# Polarization_Contol.net
KiCad netlist of a schematic drawn in EasyEDA
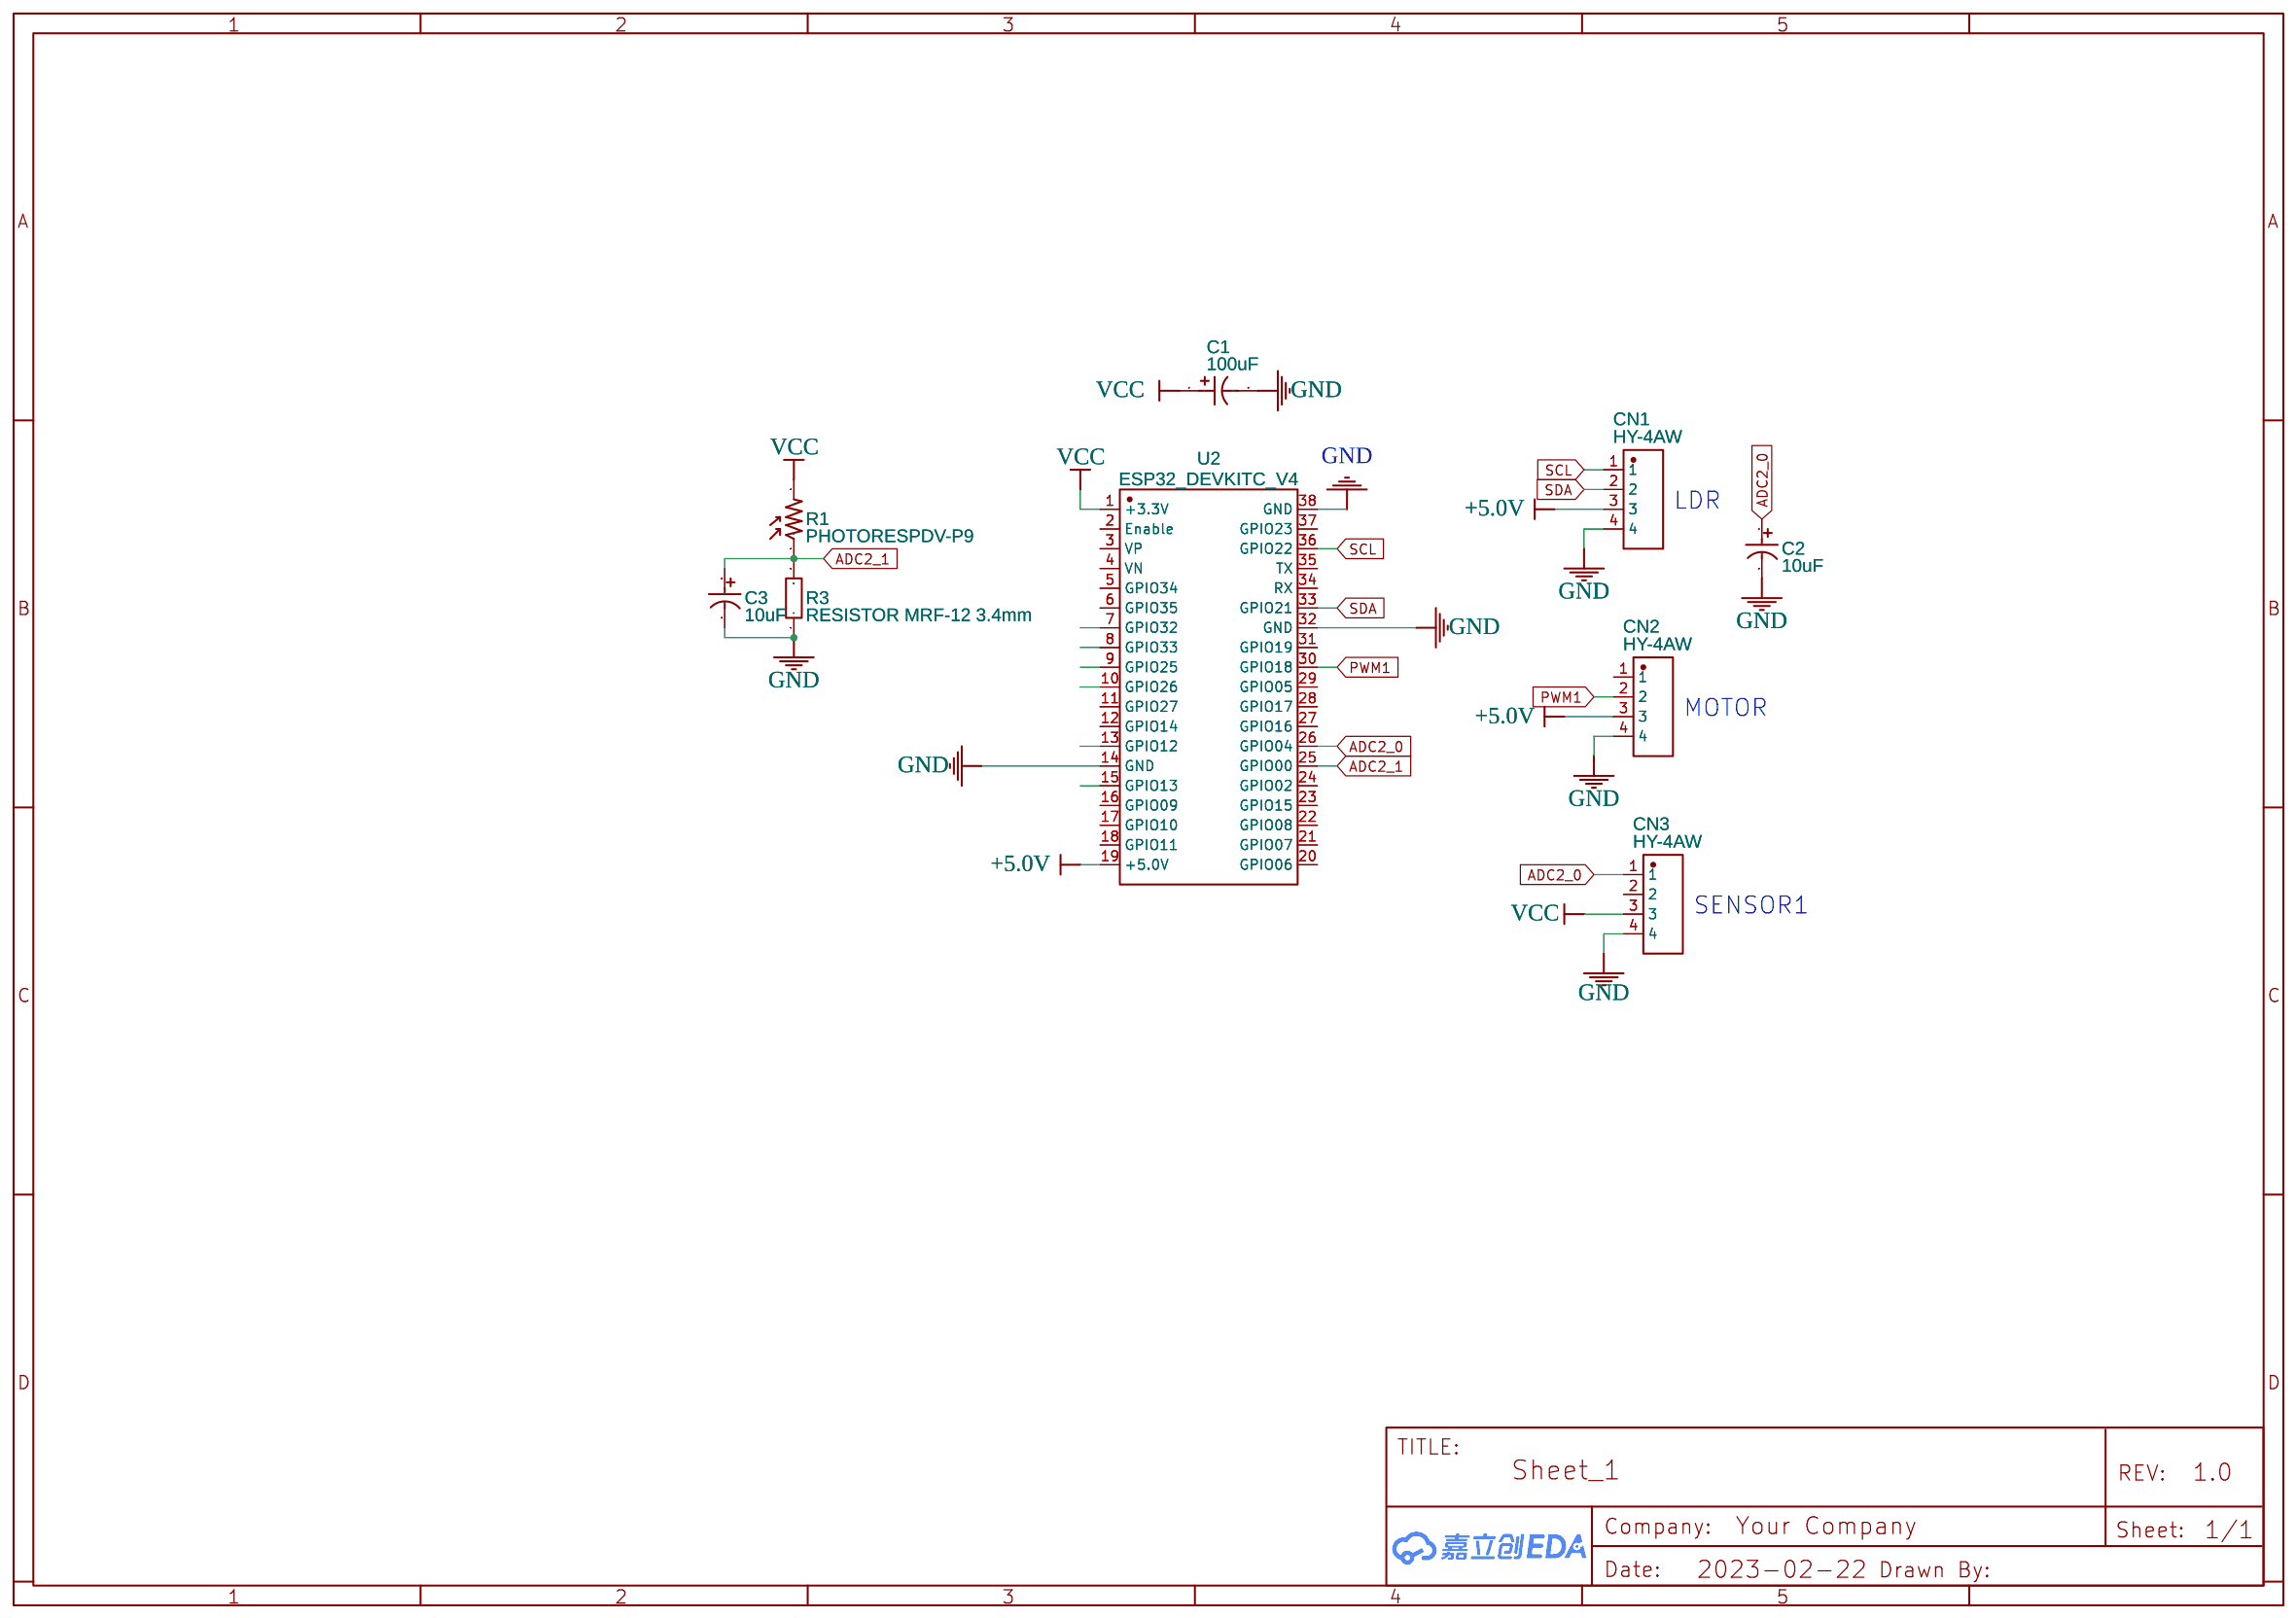
[diagram p0: Sheet_1]
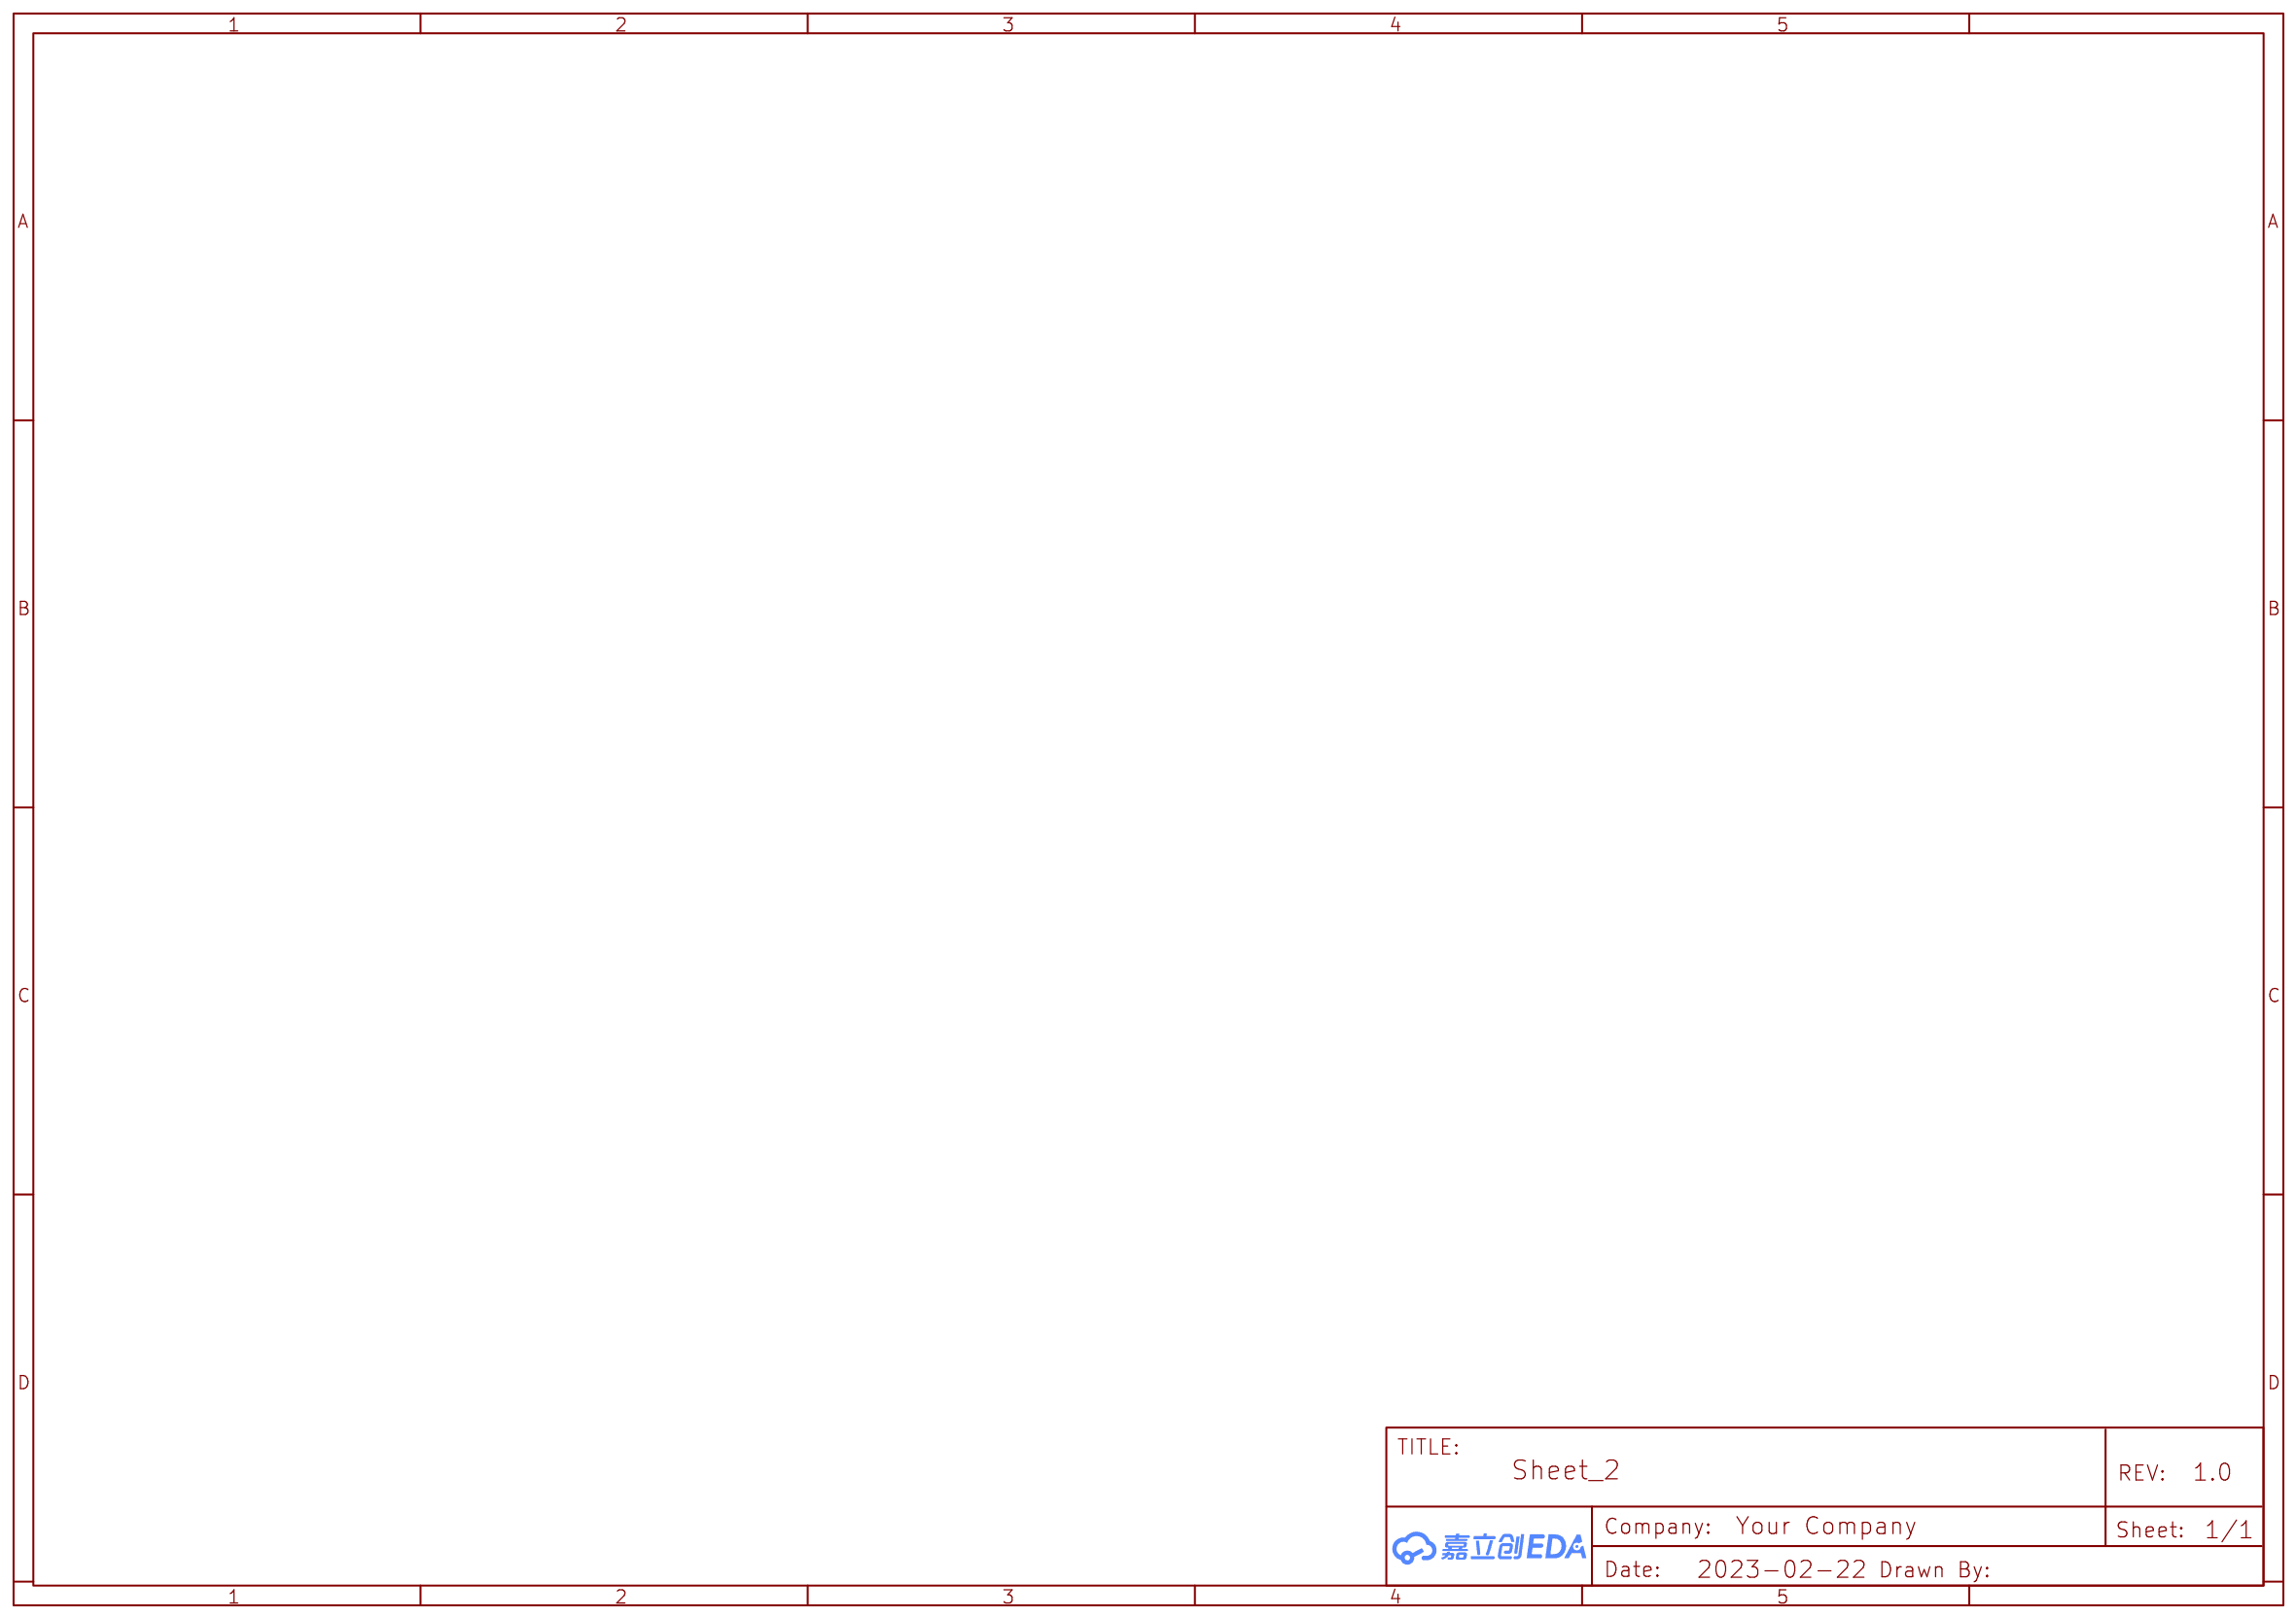
[diagram p1: Sheet_2]

(export (version "E")
  (design (tool "Eeschema 10.0.6"))
  (components
    (comp (ref "C1")
      (value "100uF")
      (fields
        (field (name "BOM_Manufacturer Part") "25V100uF CD110")
        (field (name "BOM_Supplier Part") "C2960218")
      )
      (libsource (lib "") (part "25V100UF CD110"))
    )
    (comp (ref "C2")
      (value "10uF")
      (fields
        (field (name "BOM_Manufacturer Part") "KM476M016D11RR0VH2FP0")
        (field (name "BOM_Supplier Part") "C22320")
      )
      (libsource (lib "") (part "47uF 16V Aluminum electrolytic capacitors"))
    )
    (comp (ref "C3")
      (value "10uF")
      (fields
        (field (name "BOM_Manufacturer Part") "KM476M016D11RR0VH2FP0")
        (field (name "BOM_Supplier Part") "C22320")
      )
      (libsource (lib "") (part "47uF 16V Aluminum electrolytic capacitors"))
    )
    (comp (ref "CN1")
      (value "HY-4AW")
      (fields (field (name "BOM_Supplier Part") "C146068"))
      (libsource (lib "") (part "HY-4AW"))
    )
    (comp (ref "CN2")
      (value "HY-4AW")
      (fields (field (name "BOM_Supplier Part") "C146068"))
      (libsource (lib "") (part "HY-4AW"))
    )
    (comp (ref "CN3")
      (value "HY-4AW")
      (fields (field (name "BOM_Supplier Part") "C146068"))
      (libsource (lib "") (part "HY-4AW"))
    )
    (comp (ref "R1") (value "PHOTORESPDV-P9") (libsource (lib "") (part "PHOTORESPDV-P9")))
    (comp (ref "R3") (value "RESISTOR MRF-12 3.4mm") (libsource (lib "") (part "RESISTOR MRF-12 3.4mm")))
    (comp (ref "U2")
      (value "ESP32_DEVKITC_V4")
      (fields (field (name "BOM_Supplier Part") "A5130"))
      (libsource (lib "") (part "ESP32_DEVKITC_V4"))
    )
  )
  (nets
    (net (code "1") (name "+5.0V") (class "Default")
      (node (ref "CN1") (pin "3") (pinfunction "3_3") (pintype "unspecified"))
      (node (ref "CN2") (pin "3") (pinfunction "3_3") (pintype "unspecified"))
      (node (ref "U2") (pin "19") (pinfunction "+5.0V_19") (pintype "unspecified"))
    )
    (net (code "2") (name "ADC2_0") (class "Default")
      (node (ref "C2") (pin "1") (pinfunction "1_1") (pintype "input"))
      (node (ref "CN3") (pin "1") (pinfunction "1_1") (pintype "unspecified"))
      (node (ref "U2") (pin "26") (pinfunction "GPIO04_26") (pintype "unspecified"))
    )
    (net (code "3") (name "ADC2_1") (class "Default")
      (node (ref "C3") (pin "1") (pinfunction "1_1") (pintype "input"))
      (node (ref "R1") (pin "1") (pinfunction "1_1") (pintype "unspecified"))
      (node (ref "R3") (pin "2") (pinfunction "2_2") (pintype "unspecified"))
      (node (ref "U2") (pin "25") (pinfunction "GPIO00_25") (pintype "unspecified"))
    )
    (net (code "4") (name "GND") (class "Default")
      (node (ref "C1") (pin "2") (pinfunction "2_2") (pintype "input"))
      (node (ref "C2") (pin "2") (pinfunction "2_2") (pintype "input"))
      (node (ref "C3") (pin "2") (pinfunction "2_2") (pintype "input"))
      (node (ref "CN1") (pin "4") (pinfunction "4_4") (pintype "unspecified"))
      (node (ref "CN2") (pin "4") (pinfunction "4_4") (pintype "unspecified"))
      (node (ref "CN3") (pin "4") (pinfunction "4_4") (pintype "unspecified"))
      (node (ref "R3") (pin "1") (pinfunction "1_1") (pintype "unspecified"))
      (node (ref "U2") (pin "14") (pinfunction "GND_14") (pintype "unspecified"))
      (node (ref "U2") (pin "32") (pinfunction "GND_32") (pintype "unspecified"))
      (node (ref "U2") (pin "38") (pinfunction "GND_38") (pintype "unspecified"))
    )
    (net (code "5") (name "PWM1") (class "Default")
      (node (ref "CN2") (pin "2") (pinfunction "2_2") (pintype "unspecified"))
      (node (ref "U2") (pin "30") (pinfunction "GPIO18_30") (pintype "unspecified"))
    )
    (net (code "6") (name "SCL") (class "Default")
      (node (ref "CN1") (pin "1") (pinfunction "1_1") (pintype "unspecified"))
      (node (ref "U2") (pin "36") (pinfunction "GPIO22_36") (pintype "unspecified"))
    )
    (net (code "7") (name "SDA") (class "Default")
      (node (ref "CN1") (pin "2") (pinfunction "2_2") (pintype "unspecified"))
      (node (ref "U2") (pin "33") (pinfunction "GPIO21_33") (pintype "unspecified"))
    )
    (net (code "8") (name "VCC") (class "Default")
      (node (ref "C1") (pin "1") (pinfunction "1_1") (pintype "input"))
      (node (ref "CN3") (pin "3") (pinfunction "3_3") (pintype "unspecified"))
      (node (ref "R1") (pin "2") (pinfunction "2_2") (pintype "unspecified"))
      (node (ref "U2") (pin "1") (pinfunction "+3.3V_1") (pintype "unspecified"))
    )
    (net (code "9") (name "unconnected-(CN2-Pad1)") (class "Default")
      (node (ref "CN2") (pin "1") (pinfunction "1_1") (pintype "unspecified"))
    )
    (net (code "10") (name "unconnected-(CN3-Pad2)") (class "Default")
      (node (ref "CN3") (pin "2") (pinfunction "2_2") (pintype "unspecified"))
    )
    (net (code "11") (name "unconnected-(U2-Enable-Pad2)") (class "Default")
      (node (ref "U2") (pin "2") (pinfunction "Enable_2") (pintype "unspecified"))
    )
    (net (code "12") (name "unconnected-(U2-GPIO02-Pad24)") (class "Default")
      (node (ref "U2") (pin "24") (pinfunction "GPIO02_24") (pintype "unspecified"))
    )
    (net (code "13") (name "unconnected-(U2-GPIO05-Pad29)") (class "Default")
      (node (ref "U2") (pin "29") (pinfunction "GPIO05_29") (pintype "unspecified"))
    )
    (net (code "14") (name "unconnected-(U2-GPIO06-Pad20)") (class "Default")
      (node (ref "U2") (pin "20") (pinfunction "GPIO06_20") (pintype "unspecified"))
    )
    (net (code "15") (name "unconnected-(U2-GPIO07-Pad21)") (class "Default")
      (node (ref "U2") (pin "21") (pinfunction "GPIO07_21") (pintype "unspecified"))
    )
    (net (code "16") (name "unconnected-(U2-GPIO08-Pad22)") (class "Default")
      (node (ref "U2") (pin "22") (pinfunction "GPIO08_22") (pintype "unspecified"))
    )
    (net (code "17") (name "unconnected-(U2-GPIO09-Pad16)") (class "Default")
      (node (ref "U2") (pin "16") (pinfunction "GPIO09_16") (pintype "unspecified"))
    )
    (net (code "18") (name "unconnected-(U2-GPIO10-Pad17)") (class "Default")
      (node (ref "U2") (pin "17") (pinfunction "GPIO10_17") (pintype "unspecified"))
    )
    (net (code "19") (name "unconnected-(U2-GPIO11-Pad18)") (class "Default")
      (node (ref "U2") (pin "18") (pinfunction "GPIO11_18") (pintype "unspecified"))
    )
    (net (code "20") (name "unconnected-(U2-GPIO12-Pad13)") (class "Default")
      (node (ref "U2") (pin "13") (pinfunction "GPIO12_13") (pintype "unspecified"))
    )
    (net (code "21") (name "unconnected-(U2-GPIO13-Pad15)") (class "Default")
      (node (ref "U2") (pin "15") (pinfunction "GPIO13_15") (pintype "unspecified"))
    )
    (net (code "22") (name "unconnected-(U2-GPIO14-Pad12)") (class "Default")
      (node (ref "U2") (pin "12") (pinfunction "GPIO14_12") (pintype "unspecified"))
    )
    (net (code "23") (name "unconnected-(U2-GPIO15-Pad23)") (class "Default")
      (node (ref "U2") (pin "23") (pinfunction "GPIO15_23") (pintype "unspecified"))
    )
    (net (code "24") (name "unconnected-(U2-GPIO16-Pad27)") (class "Default")
      (node (ref "U2") (pin "27") (pinfunction "GPIO16_27") (pintype "unspecified"))
    )
    (net (code "25") (name "unconnected-(U2-GPIO17-Pad28)") (class "Default")
      (node (ref "U2") (pin "28") (pinfunction "GPIO17_28") (pintype "unspecified"))
    )
    (net (code "26") (name "unconnected-(U2-GPIO19-Pad31)") (class "Default")
      (node (ref "U2") (pin "31") (pinfunction "GPIO19_31") (pintype "unspecified"))
    )
    (net (code "27") (name "unconnected-(U2-GPIO23-Pad37)") (class "Default")
      (node (ref "U2") (pin "37") (pinfunction "GPIO23_37") (pintype "unspecified"))
    )
    (net (code "28") (name "unconnected-(U2-GPIO25-Pad9)") (class "Default")
      (node (ref "U2") (pin "9") (pinfunction "GPIO25_9") (pintype "unspecified"))
    )
    (net (code "29") (name "unconnected-(U2-GPIO26-Pad10)") (class "Default")
      (node (ref "U2") (pin "10") (pinfunction "GPIO26_10") (pintype "unspecified"))
    )
    (net (code "30") (name "unconnected-(U2-GPIO27-Pad11)") (class "Default")
      (node (ref "U2") (pin "11") (pinfunction "GPIO27_11") (pintype "unspecified"))
    )
    (net (code "31") (name "unconnected-(U2-GPIO32-Pad7)") (class "Default")
      (node (ref "U2") (pin "7") (pinfunction "GPIO32_7") (pintype "unspecified"))
    )
    (net (code "32") (name "unconnected-(U2-GPIO33-Pad8)") (class "Default")
      (node (ref "U2") (pin "8") (pinfunction "GPIO33_8") (pintype "unspecified"))
    )
    (net (code "33") (name "unconnected-(U2-GPIO34-Pad5)") (class "Default")
      (node (ref "U2") (pin "5") (pinfunction "GPIO34_5") (pintype "unspecified"))
    )
    (net (code "34") (name "unconnected-(U2-GPIO35-Pad6)") (class "Default")
      (node (ref "U2") (pin "6") (pinfunction "GPIO35_6") (pintype "unspecified"))
    )
    (net (code "35") (name "unconnected-(U2-RX-Pad34)") (class "Default")
      (node (ref "U2") (pin "34") (pinfunction "RX_34") (pintype "unspecified"))
    )
    (net (code "36") (name "unconnected-(U2-TX-Pad35)") (class "Default")
      (node (ref "U2") (pin "35") (pinfunction "TX_35") (pintype "unspecified"))
    )
    (net (code "37") (name "unconnected-(U2-VN-Pad4)") (class "Default")
      (node (ref "U2") (pin "4") (pinfunction "VN_4") (pintype "unspecified"))
    )
    (net (code "38") (name "unconnected-(U2-VP-Pad3)") (class "Default")
      (node (ref "U2") (pin "3") (pinfunction "VP_3") (pintype "unspecified"))
    )
  )
)
